# Sheet1.net
KiCad netlist of a schematic drawn in Altium Designer
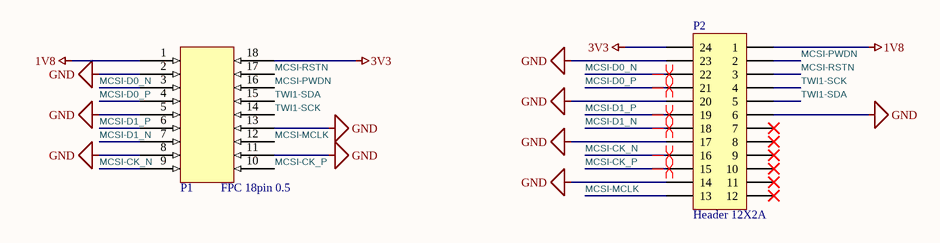
[diagram p0: Sheet1.SchDoc]

(export (version "E")
  (design (tool "Eeschema 10.0.6"))
  (components
    (comp (ref "P1")
      (value "FPC 18pin 0.5")
      (footprint "FPC 18pin 0.5")
      (libsource (lib "maix_2") (part "FPC 18pin 0.5"))
    )
    (comp (ref "P2")
      (value "Header 12X2A")
      (footprint "BTB 24PIN")
      (description "Header, 12-Pin, Dual row")
      (fields (field (name "PUBLISHER") "Altium Limited"))
      (libsource (lib "Schlib1") (part "Header 12X2A"))
    )
  )
  (nets
    (net (code "1") (name "/MCSI-CK_N") (class "Default")
      (node (ref "P1") (pin "9") (pintype "input"))
      (node (ref "P2") (pin "16") (pinfunction "16_16") (pintype "passive"))
    )
    (net (code "2") (name "/MCSI-CK_P") (class "Default")
      (node (ref "P1") (pin "10") (pintype "input"))
      (node (ref "P2") (pin "15") (pinfunction "15_15") (pintype "passive"))
    )
    (net (code "3") (name "/MCSI-D0_N") (class "Default")
      (node (ref "P1") (pin "3") (pintype "input"))
      (node (ref "P2") (pin "22") (pinfunction "22_22") (pintype "passive"))
    )
    (net (code "4") (name "/MCSI-D0_P") (class "Default")
      (node (ref "P1") (pin "4") (pintype "input"))
      (node (ref "P2") (pin "21") (pinfunction "21_21") (pintype "passive"))
    )
    (net (code "5") (name "/MCSI-D1_N") (class "Default")
      (node (ref "P1") (pin "7") (pintype "input"))
      (node (ref "P2") (pin "18") (pinfunction "18_18") (pintype "passive"))
    )
    (net (code "6") (name "/MCSI-D1_P") (class "Default")
      (node (ref "P1") (pin "6") (pintype "input"))
      (node (ref "P2") (pin "19") (pinfunction "19_19") (pintype "passive"))
    )
    (net (code "7") (name "/MCSI-MCLK") (class "Default")
      (node (ref "P1") (pin "12") (pintype "input"))
      (node (ref "P2") (pin "13") (pinfunction "13_13") (pintype "passive"))
    )
    (net (code "8") (name "/MCSI-PWDN") (class "Default")
      (node (ref "P1") (pin "16") (pintype "input"))
      (node (ref "P2") (pin "2") (pinfunction "2_2") (pintype "passive"))
    )
    (net (code "9") (name "/MCSI-RSTN") (class "Default")
      (node (ref "P1") (pin "17") (pintype "input"))
      (node (ref "P2") (pin "3") (pinfunction "3_3") (pintype "passive"))
    )
    (net (code "10") (name "/TWI1-SCK") (class "Default")
      (node (ref "P1") (pin "14") (pintype "input"))
      (node (ref "P2") (pin "4") (pinfunction "4_4") (pintype "passive"))
    )
    (net (code "11") (name "/TWI1-SDA") (class "Default")
      (node (ref "P1") (pin "15") (pintype "input"))
      (node (ref "P2") (pin "5") (pinfunction "5_5") (pintype "passive"))
    )
    (net (code "12") (name "1V8") (class "Default")
      (node (ref "P1") (pin "1") (pintype "input"))
      (node (ref "P2") (pin "1") (pinfunction "1_1") (pintype "passive"))
    )
    (net (code "13") (name "3V3") (class "Default")
      (node (ref "P1") (pin "18") (pintype "input"))
      (node (ref "P2") (pin "24") (pinfunction "24_24") (pintype "passive"))
    )
    (net (code "14") (name "GND") (class "Default")
      (node (ref "P1") (pin "11") (pintype "input"))
      (node (ref "P1") (pin "13") (pintype "input"))
      (node (ref "P1") (pin "2") (pintype "input"))
      (node (ref "P1") (pin "5") (pintype "input"))
      (node (ref "P1") (pin "8") (pintype "input"))
      (node (ref "P2") (pin "14") (pinfunction "14_14") (pintype "passive"))
      (node (ref "P2") (pin "17") (pinfunction "17_17") (pintype "passive"))
      (node (ref "P2") (pin "20") (pinfunction "20_20") (pintype "passive"))
      (node (ref "P2") (pin "23") (pinfunction "23_23") (pintype "passive"))
      (node (ref "P2") (pin "6") (pinfunction "6_6") (pintype "passive"))
    )
    (net (code "15") (name "unconnected-(P2-Pad7)") (class "Default")
      (node (ref "P2") (pin "7") (pinfunction "7_7") (pintype "passive+no_connect"))
    )
    (net (code "16") (name "unconnected-(P2-Pad8)") (class "Default")
      (node (ref "P2") (pin "8") (pinfunction "8_8") (pintype "passive+no_connect"))
    )
    (net (code "17") (name "unconnected-(P2-Pad9)") (class "Default")
      (node (ref "P2") (pin "9") (pinfunction "9_9") (pintype "passive+no_connect"))
    )
    (net (code "18") (name "unconnected-(P2-Pad10)") (class "Default")
      (node (ref "P2") (pin "10") (pinfunction "10_10") (pintype "passive+no_connect"))
    )
    (net (code "19") (name "unconnected-(P2-Pad11)") (class "Default")
      (node (ref "P2") (pin "11") (pinfunction "11_11") (pintype "passive+no_connect"))
    )
    (net (code "20") (name "unconnected-(P2-Pad12)") (class "Default")
      (node (ref "P2") (pin "12") (pinfunction "12_12") (pintype "passive+no_connect"))
    )
  )
)
